# Booster.net
KiCad netlist of a schematic drawn in Altium Designer
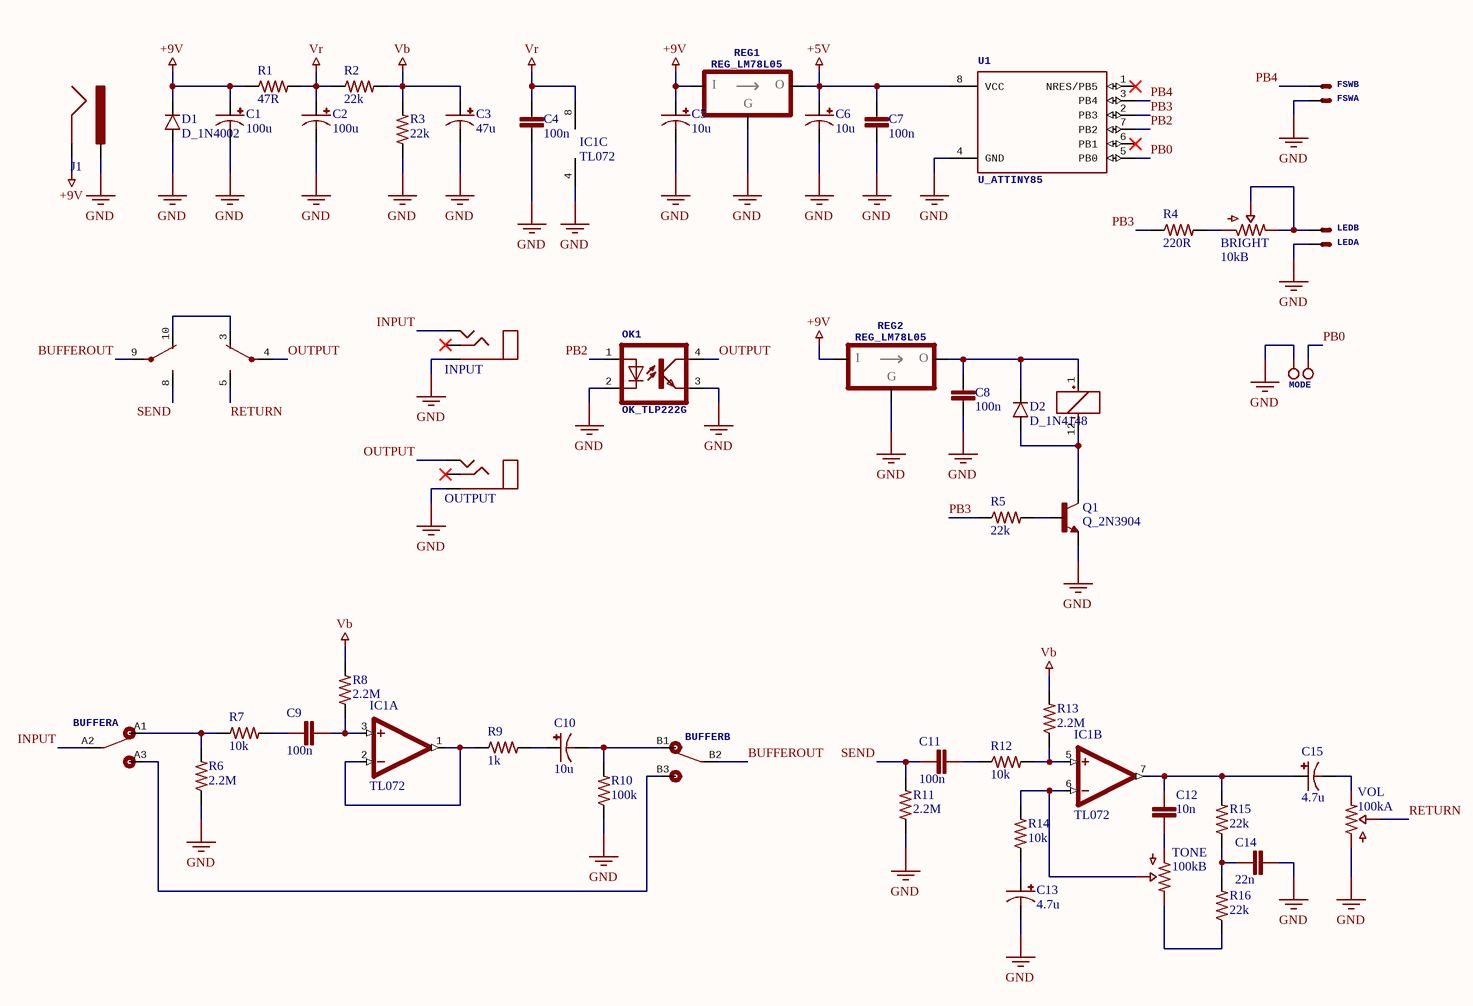
[diagram p0: Booster.SchDoc]

(export (version "E")
  (design (tool "Eeschema 10.0.6"))
  (components
    (comp (ref "BRIGHT")
      (value "10kB")
      (footprint "BOURNS_3362P")
      (description "10k Lin 3362P trimmer")
      (libsource (lib "Pedals") (part "TRIM_10kB_3362P"))
    )
    (comp (ref "BUFFER")
      (value "DPDT")
      (footprint "DPDT_SLIDE")
      (description "DPDT slide switch ON/ON")
      (libsource (lib "Pedals") (part "SW_SLIDE_DPDT_ON-ON"))
    )
    (comp (ref "C1")
      (value "100u")
      (footprint "ELEC_063_025")
      (description "100u 25V electrolytic capacitor")
      (libsource (lib "Pedals") (part "C_ELEC_100u_25V"))
    )
    (comp (ref "C2")
      (value "100u")
      (footprint "ELEC_063_025")
      (description "100u 25V electrolytic capacitor")
      (libsource (lib "Pedals") (part "C_ELEC_100u_25V"))
    )
    (comp (ref "C3")
      (value "47u")
      (footprint "ELEC_050_020")
      (description "47u 25V electrolytic capacitor")
      (libsource (lib "Pedals") (part "C_ELEC_47u_25V"))
    )
    (comp (ref "C4")
      (value "100n")
      (footprint "CER_050")
      (description "100n MLCC X7R radial capacitor")
      (libsource (lib "Pedals") (part "C_CER_100n"))
    )
    (comp (ref "C5")
      (value "10u")
      (footprint "ELEC_050_020")
      (description "10u 50V electrolytic capacitor")
      (libsource (lib "Pedals") (part "C_ELEC_10u_50V"))
    )
    (comp (ref "C6")
      (value "10u")
      (footprint "ELEC_050_020")
      (description "10u 50V electrolytic capacitor")
      (libsource (lib "Pedals") (part "C_ELEC_10u_50V"))
    )
    (comp (ref "C7")
      (value "100n")
      (footprint "CER_050")
      (description "100n MLCC X7R radial capacitor")
      (libsource (lib "") (part "C_CER_100n_1"))
    )
    (comp (ref "C8")
      (value "100n")
      (footprint "CER_050")
      (description "100n MLCC X7R radial capacitor")
      (libsource (lib "Pedals") (part "C_CER_100n"))
    )
    (comp (ref "C9")
      (value "100n")
      (footprint "FILMBOX_SMALL")
      (description "100n 100V polyester film box capacitor")
      (libsource (lib "Pedals") (part "C_FILMBOX_100n"))
    )
    (comp (ref "C10")
      (value "10u")
      (footprint "ELEC_LESR_050_020")
      (description "10u 50V Low ESR ectrolytic capacitor")
      (libsource (lib "Pedals") (part "C_ELEC_LESR_10u_50V"))
    )
    (comp (ref "C11")
      (value "100n")
      (footprint "FILMBOX_SMALL")
      (description "100n 100V polyester film box capacitor")
      (libsource (lib "Pedals") (part "C_FILMBOX_100n"))
    )
    (comp (ref "C12")
      (value "10n")
      (footprint "FILMBOX_SMALL")
      (description "10n 100V polyester film box capacitor")
      (libsource (lib "Pedals") (part "C_FILMBOX_10n"))
    )
    (comp (ref "C13")
      (value "4.7u")
      (footprint "ELEC_LESR_050_020")
      (description "4.7u 50V Low ESR ectrolytic capacitor")
      (libsource (lib "") (part "C_ELEC_LESR_4.7u_50V_1"))
    )
    (comp (ref "C14")
      (value "22n")
      (footprint "FILMBOX_SMALL")
      (description "22n 100V polyester film box capacitor")
      (libsource (lib "Pedals") (part "C_FILMBOX_22n"))
    )
    (comp (ref "C15")
      (value "4.7u")
      (footprint "ELEC_LESR_050_020")
      (description "4.7u 50V Low ESR ectrolytic capacitor")
      (libsource (lib "Pedals") (part "C_ELEC_LESR_4.7u_50V"))
    )
    (comp (ref "D1")
      (value "D_1N4002")
      (footprint "DO41_2")
      (description "1N4002")
      (libsource (lib "Pedals") (part "D_1N4002"))
    )
    (comp (ref "D2")
      (value "D_1N4148")
      (footprint "DO35_2")
      (description "1N4148")
      (libsource (lib "Pedals") (part "D_1N4148"))
    )
    (comp (ref "FSW")
      (value "J_JST-XH-02")
      (footprint "JST-XH-02")
      (description "2 Pins male XH header")
      (libsource (lib "Pedals") (part "J_JST-XH-02"))
    )
    (comp (ref "IC1") (value "TL072") (footprint "DIL8") (libsource (lib "Pedals") (part "IC_TL072")))
    (comp (ref "INPUT")
      (value "J_STEREO")
      (footprint "STEREO")
      (description "6.35mm stereo insulated socket jack PCB mounted")
      (libsource (lib "Pedals") (part "J_STEREO"))
    )
    (comp (ref "J1")
      (value "J_DC_JACK")
      (footprint "DC_JACK")
      (description "DC Power jack 2.1mm barrel")
      (libsource (lib "Pedals") (part "J_DC_JACK"))
    )
    (comp (ref "K1")
      (value "K_NA5W-K")
      (footprint "NA5")
      (description "NA5W-K")
      (libsource (lib "Pedals") (part "K_NA5W-K"))
    )
    (comp (ref "LED")
      (value "J_JST-XH-02")
      (footprint "JST-XH-02")
      (description "2 Pins male XH header")
      (libsource (lib "Pedals") (part "J_JST-XH-02"))
    )
    (comp (ref "MODE")
      (value "J_HEADER_2PINS")
      (footprint "HEADER_2PINS")
      (description "2 Pins male header")
      (libsource (lib "Pedals") (part "J_HEADER_2PINS"))
    )
    (comp (ref "OK1")
      (value "OK_TLP222G")
      (footprint "DIL4")
      (description "TLP222G")
      (libsource (lib "Pedals") (part "OK_TLP222G"))
    )
    (comp (ref "OUTPUT")
      (value "J_STEREO")
      (footprint "STEREO")
      (description "6.35mm stereo insulated socket jack PCB mounted")
      (libsource (lib "Pedals") (part "J_STEREO"))
    )
    (comp (ref "Q1")
      (value "Q_2N3904")
      (footprint "TO92")
      (description "2N3904")
      (libsource (lib "Pedals") (part "Q_2N3904"))
    )
    (comp (ref "R1")
      (value "47R")
      (footprint "R_3_47R_025W")
      (description "47R metal film 1/4W Resistor")
      (libsource (lib "Pedals") (part "R_3_47R_025W"))
    )
    (comp (ref "R2")
      (value "22k")
      (footprint "R_3_22k_025W")
      (description "22k metal film 1/4W Resistor")
      (libsource (lib "Pedals") (part "R_3_22k_025W"))
    )
    (comp (ref "R3")
      (value "22k")
      (footprint "R_3_22k_025W")
      (description "22k metal film 1/4W Resistor")
      (libsource (lib "Pedals") (part "R_3_22k_025W"))
    )
    (comp (ref "R4")
      (value "220R")
      (footprint "R_3_220R_025W")
      (description "220R metal film 1/4W Resistor")
      (libsource (lib "Pedals") (part "R_3_220R_025W"))
    )
    (comp (ref "R5")
      (value "22k")
      (footprint "R_3_22k_025W")
      (description "22k metal film 1/4W Resistor")
      (libsource (lib "Pedals") (part "R_3_22k_025W"))
    )
    (comp (ref "R6")
      (value "2.2M")
      (footprint "R_3_2,2M_025W")
      (description "2.2M metal film 1/4W Resistor")
      (libsource (lib "Pedals") (part "R_3_2.2M_025W"))
    )
    (comp (ref "R7")
      (value "10k")
      (footprint "R_3_10k_025W")
      (description "10k metal film 1/4W Resistor")
      (libsource (lib "Pedals") (part "R_3_10k_025W"))
    )
    (comp (ref "R8")
      (value "2.2M")
      (footprint "R_3_2,2M_025W")
      (description "2.2M metal film 1/4W Resistor")
      (libsource (lib "Pedals") (part "R_3_2.2M_025W"))
    )
    (comp (ref "R9")
      (value "1k")
      (footprint "R_3_1k_025W")
      (description "1k metal film 1/4W Resistor")
      (libsource (lib "Pedals") (part "R_3_1k_025W"))
    )
    (comp (ref "R10")
      (value "100k")
      (footprint "R_3_100k_025W")
      (description "100k metal film 1/4W Resistor")
      (libsource (lib "Pedals") (part "R_3_100k_025W"))
    )
    (comp (ref "R11")
      (value "2.2M")
      (footprint "R_3_2,2M_025W")
      (description "2.2M metal film 1/4W Resistor")
      (libsource (lib "Pedals") (part "R_3_2.2M_025W"))
    )
    (comp (ref "R12")
      (value "10k")
      (footprint "R_3_10k_025W")
      (description "10k metal film 1/4W Resistor")
      (libsource (lib "Pedals") (part "R_3_10k_025W"))
    )
    (comp (ref "R13")
      (value "2.2M")
      (footprint "R_3_2,2M_025W")
      (description "2.2M metal film 1/4W Resistor")
      (libsource (lib "Pedals") (part "R_3_2.2M_025W"))
    )
    (comp (ref "R14")
      (value "10k")
      (footprint "R_3_10k_025W")
      (description "10k metal film 1/4W Resistor")
      (libsource (lib "Pedals") (part "R_3_10k_025W"))
    )
    (comp (ref "R15")
      (value "22k")
      (footprint "R_3_22k_025W")
      (description "22k metal film 1/4W Resistor")
      (libsource (lib "Pedals") (part "R_3_22k_025W"))
    )
    (comp (ref "R16")
      (value "22k")
      (footprint "R_3_22k_025W")
      (description "22k metal film 1/4W Resistor")
      (libsource (lib "Pedals") (part "R_3_22k_025W"))
    )
    (comp (ref "REG1")
      (value "REG_LM78L05")
      (footprint "TO92")
      (description "78L05")
      (libsource (lib "Pedals") (part "REG_LM78L05"))
    )
    (comp (ref "REG2")
      (value "REG_LM78L05")
      (footprint "TO92")
      (description "78L05")
      (libsource (lib "Pedals") (part "REG_LM78L05"))
    )
    (comp (ref "TONE")
      (value "100kB")
      (footprint "ALPHA_16mm_BOTTOM")
      (description "100k Lin potentiometer round shaft")
      (libsource (lib "Pedals") (part "POT_100kB_ALPHA_16mm"))
    )
    (comp (ref "U1")
      (value "U_ATTINY85")
      (footprint "DIP8")
      (description "ATTINY85-20PU")
      (libsource (lib "Pedals") (part "U_ATTINY85"))
    )
    (comp (ref "VOL")
      (value "100kA")
      (footprint "ALPHA_16mm_BOTTOM")
      (description "100k Log potentiometer round shaft")
      (libsource (lib "Pedals") (part "POT_100kA_ALPHA_16mm"))
    )
  )
  (nets
    (net (code "1") (name "+5V") (class "Default")
      (node (ref "C6") (pin "+") (pinfunction "+_+") (pintype "passive"))
      (node (ref "C7") (pin "2") (pinfunction "2_2") (pintype "passive"))
      (node (ref "REG1") (pin "3") (pinfunction "VO_3") (pintype "power_in"))
      (node (ref "U1") (pin "8") (pinfunction "VCC_8") (pintype "power_in"))
    )
    (net (code "2") (name "+9V") (class "Default")
      (node (ref "C1") (pin "+") (pinfunction "+_+") (pintype "passive"))
      (node (ref "C5") (pin "+") (pinfunction "+_+") (pintype "passive"))
      (node (ref "D1") (pin "C") (pinfunction "C_C") (pintype "passive"))
      (node (ref "J1") (pin "GND") (pinfunction "GND_GND") (pintype "passive"))
      (node (ref "R1") (pin "1") (pinfunction "1_1") (pintype "passive"))
      (node (ref "REG1") (pin "1") (pinfunction "VI_1") (pintype "power_in"))
      (node (ref "REG2") (pin "1") (pinfunction "VI_1") (pintype "power_in"))
    )
    (net (code "3") (name "/BUFFEROUT") (class "Default")
      (node (ref "BUFFER") (pin "B2") (pinfunction "2_B2") (pintype "passive"))
      (node (ref "K1") (pin "9") (pinfunction "P_9") (pintype "passive"))
    )
    (net (code "4") (name "/INPUT") (class "Default")
      (node (ref "BUFFER") (pin "A2") (pinfunction "2_A2") (pintype "passive"))
      (node (ref "INPUT") (pin "T") (pinfunction "T_T") (pintype "passive"))
    )
    (net (code "5") (name "/OUTPUT") (class "Default")
      (node (ref "K1") (pin "4") (pinfunction "P_4") (pintype "passive"))
      (node (ref "OK1") (pin "4") (pinfunction "COL_4") (pintype "passive"))
      (node (ref "OUTPUT") (pin "T") (pinfunction "T_T") (pintype "passive"))
    )
    (net (code "6") (name "/PB0") (class "Default")
      (node (ref "MODE") (pin "2") (pinfunction "2_2") (pintype "passive"))
      (node (ref "U1") (pin "5") (pinfunction "PB0_5") (pintype "bidirectional"))
    )
    (net (code "7") (name "/PB2") (class "Default")
      (node (ref "OK1") (pin "1") (pinfunction "A_1") (pintype "passive"))
      (node (ref "U1") (pin "7") (pinfunction "PB2_7") (pintype "bidirectional"))
    )
    (net (code "8") (name "/PB3") (class "Default")
      (node (ref "R4") (pin "1") (pinfunction "1_1") (pintype "passive"))
      (node (ref "R5") (pin "1") (pinfunction "1_1") (pintype "passive"))
      (node (ref "U1") (pin "2") (pinfunction "PB3_2") (pintype "bidirectional"))
    )
    (net (code "9") (name "/PB4") (class "Default")
      (node (ref "FSW") (pin "1") (pinfunction "S_1") (pintype "passive"))
      (node (ref "U1") (pin "3") (pinfunction "PB4_3") (pintype "bidirectional"))
    )
    (net (code "10") (name "/RETURN") (class "Default")
      (node (ref "K1") (pin "5") (pinfunction "S_5") (pintype "passive"))
      (node (ref "VOL") (pin "2") (pinfunction "2_2") (pintype "passive"))
    )
    (net (code "11") (name "/SEND") (class "Default")
      (node (ref "C11") (pin "2") (pinfunction "2_2") (pintype "passive"))
      (node (ref "K1") (pin "8") (pinfunction "S_8") (pintype "passive"))
      (node (ref "R11") (pin "2") (pinfunction "2_2") (pintype "passive"))
    )
    (net (code "12") (name "GND") (class "Default")
      (node (ref "C1") (pin "-") (pinfunction "-_-") (pintype "passive"))
      (node (ref "C13") (pin "-") (pinfunction "-_-") (pintype "passive"))
      (node (ref "C14") (pin "1") (pinfunction "1_1") (pintype "passive"))
      (node (ref "C2") (pin "-") (pinfunction "-_-") (pintype "passive"))
      (node (ref "C3") (pin "-") (pinfunction "-_-") (pintype "passive"))
      (node (ref "C4") (pin "2") (pinfunction "2_2") (pintype "passive"))
      (node (ref "C5") (pin "-") (pinfunction "-_-") (pintype "passive"))
      (node (ref "C6") (pin "-") (pinfunction "-_-") (pintype "passive"))
      (node (ref "C7") (pin "1") (pinfunction "1_1") (pintype "passive"))
      (node (ref "C8") (pin "2") (pinfunction "2_2") (pintype "passive"))
      (node (ref "D1") (pin "A") (pinfunction "A_A") (pintype "passive"))
      (node (ref "FSW") (pin "2") (pinfunction "S_2") (pintype "passive"))
      (node (ref "IC1") (pin "4") (pinfunction "V-_4") (pintype "power_in"))
      (node (ref "INPUT") (pin "S") (pinfunction "S_S") (pintype "passive"))
      (node (ref "J1") (pin "PWR") (pinfunction "PWR_PWR") (pintype "passive"))
      (node (ref "LED") (pin "2") (pinfunction "S_2") (pintype "passive"))
      (node (ref "MODE") (pin "1") (pinfunction "1_1") (pintype "passive"))
      (node (ref "OK1") (pin "2") (pinfunction "C_2") (pintype "passive"))
      (node (ref "OK1") (pin "3") (pinfunction "EMIT_3") (pintype "passive"))
      (node (ref "OUTPUT") (pin "S") (pinfunction "S_S") (pintype "passive"))
      (node (ref "Q1") (pin "3") (pinfunction "E_3") (pintype "passive"))
      (node (ref "R10") (pin "1") (pinfunction "1_1") (pintype "passive"))
      (node (ref "R11") (pin "1") (pinfunction "1_1") (pintype "passive"))
      (node (ref "R3") (pin "1") (pinfunction "1_1") (pintype "passive"))
      (node (ref "R6") (pin "1") (pinfunction "1_1") (pintype "passive"))
      (node (ref "REG1") (pin "2") (pinfunction "GND_2") (pintype "power_in"))
      (node (ref "REG2") (pin "2") (pinfunction "GND_2") (pintype "power_in"))
      (node (ref "U1") (pin "4") (pinfunction "GND_4") (pintype "power_in"))
      (node (ref "VOL") (pin "1") (pinfunction "1_1") (pintype "passive"))
    )
    (net (code "13") (name "Net-(BRIGHT-Pad1)") (class "Default")
      (node (ref "BRIGHT") (pin "1") (pinfunction "1_1") (pintype "passive"))
      (node (ref "R4") (pin "2") (pinfunction "2_2") (pintype "passive"))
    )
    (net (code "14") (name "Net-(BUFFERA-1)") (class "Default")
      (node (ref "BUFFER") (pin "A1") (pinfunction "1_A1") (pintype "passive"))
      (node (ref "R6") (pin "2") (pinfunction "2_2") (pintype "passive"))
      (node (ref "R7") (pin "1") (pinfunction "1_1") (pintype "passive"))
    )
    (net (code "15") (name "Net-(BUFFERA-3)") (class "Default")
      (node (ref "BUFFER") (pin "A3") (pinfunction "3_A3") (pintype "passive"))
      (node (ref "BUFFER") (pin "B3") (pinfunction "3_B3") (pintype "passive"))
    )
    (net (code "16") (name "Net-(BUFFERB-1)") (class "Default")
      (node (ref "BUFFER") (pin "B1") (pinfunction "1_B1") (pintype "passive"))
      (node (ref "C10") (pin "-") (pinfunction "-_-") (pintype "passive"))
      (node (ref "R10") (pin "2") (pinfunction "2_2") (pintype "passive"))
    )
    (net (code "17") (name "Net-(C9-Pad2)") (class "Default")
      (node (ref "C9") (pin "2") (pinfunction "2_2") (pintype "passive"))
      (node (ref "R7") (pin "2") (pinfunction "2_2") (pintype "passive"))
    )
    (net (code "18") (name "Net-(C10-Pad+)") (class "Default")
      (node (ref "C10") (pin "+") (pinfunction "+_+") (pintype "passive"))
      (node (ref "R9") (pin "2") (pinfunction "2_2") (pintype "passive"))
    )
    (net (code "19") (name "Net-(C11-Pad1)") (class "Default")
      (node (ref "C11") (pin "1") (pinfunction "1_1") (pintype "passive"))
      (node (ref "R12") (pin "1") (pinfunction "1_1") (pintype "passive"))
    )
    (net (code "20") (name "Net-(C12-Pad2)") (class "Default")
      (node (ref "C12") (pin "2") (pinfunction "2_2") (pintype "passive"))
      (node (ref "TONE") (pin "1") (pinfunction "1_1") (pintype "passive"))
    )
    (net (code "21") (name "Net-(C13-Pad+)") (class "Default")
      (node (ref "C13") (pin "+") (pinfunction "+_+") (pintype "passive"))
      (node (ref "R14") (pin "1") (pinfunction "1_1") (pintype "passive"))
    )
    (net (code "22") (name "Net-(C14-Pad2)") (class "Default")
      (node (ref "C14") (pin "2") (pinfunction "2_2") (pintype "passive"))
      (node (ref "R15") (pin "1") (pinfunction "1_1") (pintype "passive"))
      (node (ref "R16") (pin "2") (pinfunction "2_2") (pintype "passive"))
    )
    (net (code "23") (name "Net-(C15-Pad-)") (class "Default")
      (node (ref "C15") (pin "-") (pinfunction "-_-") (pintype "passive"))
      (node (ref "VOL") (pin "3") (pinfunction "3_3") (pintype "passive"))
    )
    (net (code "24") (name "Net-(IC1A-+IN)") (class "Default")
      (node (ref "C9") (pin "1") (pinfunction "1_1") (pintype "passive"))
      (node (ref "IC1") (pin "3") (pinfunction "+IN_3") (pintype "input"))
      (node (ref "R8") (pin "1") (pinfunction "1_1") (pintype "passive"))
    )
    (net (code "25") (name "Net-(IC1A--IN)") (class "Default")
      (node (ref "IC1") (pin "1") (pinfunction "OUT_1") (pintype "output"))
      (node (ref "IC1") (pin "2") (pinfunction "-IN_2") (pintype "input"))
      (node (ref "R9") (pin "1") (pinfunction "1_1") (pintype "passive"))
    )
    (net (code "26") (name "Net-(IC1B-+IN)") (class "Default")
      (node (ref "IC1") (pin "5") (pinfunction "+IN_5") (pintype "input"))
      (node (ref "R12") (pin "2") (pinfunction "2_2") (pintype "passive"))
      (node (ref "R13") (pin "1") (pinfunction "1_1") (pintype "passive"))
    )
    (net (code "27") (name "Net-(IC1B--IN)") (class "Default")
      (node (ref "IC1") (pin "6") (pinfunction "-IN_6") (pintype "input"))
      (node (ref "R14") (pin "2") (pinfunction "2_2") (pintype "passive"))
      (node (ref "TONE") (pin "2") (pinfunction "2_2") (pintype "passive"))
    )
    (net (code "28") (name "Net-(IC1B-OUT)") (class "Default")
      (node (ref "C12") (pin "1") (pinfunction "1_1") (pintype "passive"))
      (node (ref "C15") (pin "+") (pinfunction "+_+") (pintype "passive"))
      (node (ref "IC1") (pin "7") (pinfunction "OUT_7") (pintype "output"))
      (node (ref "R15") (pin "2") (pinfunction "2_2") (pintype "passive"))
    )
    (net (code "29") (name "Net-(K1A-+)") (class "Default")
      (node (ref "C8") (pin "1") (pinfunction "1_1") (pintype "passive"))
      (node (ref "D2") (pin "C") (pinfunction "C_C") (pintype "passive"))
      (node (ref "K1") (pin "1") (pinfunction "+_1") (pintype "passive"))
      (node (ref "REG2") (pin "3") (pinfunction "VO_3") (pintype "power_in"))
    )
    (net (code "30") (name "Net-(K1A--)") (class "Default")
      (node (ref "D2") (pin "A") (pinfunction "A_A") (pintype "passive"))
      (node (ref "K1") (pin "12") (pinfunction "-_12") (pintype "passive"))
      (node (ref "Q1") (pin "1") (pinfunction "C_1") (pintype "passive"))
    )
    (net (code "31") (name "Net-(K1B-O)") (class "Default")
      (node (ref "K1") (pin "10") (pinfunction "O_10") (pintype "passive"))
      (node (ref "K1") (pin "3") (pinfunction "O_3") (pintype "passive"))
    )
    (net (code "32") (name "Net-(LEDB-S)") (class "Default")
      (node (ref "BRIGHT") (pin "2") (pinfunction "2_2") (pintype "passive"))
      (node (ref "BRIGHT") (pin "3") (pinfunction "3_3") (pintype "passive"))
      (node (ref "LED") (pin "1") (pinfunction "S_1") (pintype "passive"))
    )
    (net (code "33") (name "Net-(Q1-B)") (class "Default")
      (node (ref "Q1") (pin "2") (pinfunction "B_2") (pintype "passive"))
      (node (ref "R5") (pin "2") (pinfunction "2_2") (pintype "passive"))
    )
    (net (code "34") (name "Net-(R16-Pad1)") (class "Default")
      (node (ref "R16") (pin "1") (pinfunction "1_1") (pintype "passive"))
      (node (ref "TONE") (pin "3") (pinfunction "3_3") (pintype "passive"))
    )
    (net (code "35") (name "Vb") (class "Default")
      (node (ref "C3") (pin "+") (pinfunction "+_+") (pintype "passive"))
      (node (ref "R13") (pin "2") (pinfunction "2_2") (pintype "passive"))
      (node (ref "R2") (pin "2") (pinfunction "2_2") (pintype "passive"))
      (node (ref "R3") (pin "2") (pinfunction "2_2") (pintype "passive"))
      (node (ref "R8") (pin "2") (pinfunction "2_2") (pintype "passive"))
    )
    (net (code "36") (name "Vr") (class "Default")
      (node (ref "C2") (pin "+") (pinfunction "+_+") (pintype "passive"))
      (node (ref "C4") (pin "1") (pinfunction "1_1") (pintype "passive"))
      (node (ref "IC1") (pin "8") (pinfunction "V+_8") (pintype "power_in"))
      (node (ref "R1") (pin "2") (pinfunction "2_2") (pintype "passive"))
      (node (ref "R2") (pin "1") (pinfunction "1_1") (pintype "passive"))
    )
    (net (code "37") (name "unconnected-(INPUT-PadR)") (class "Default")
      (node (ref "INPUT") (pin "R") (pinfunction "R_R") (pintype "passive+no_connect"))
    )
    (net (code "38") (name "unconnected-(OUTPUT-PadR)") (class "Default")
      (node (ref "OUTPUT") (pin "R") (pinfunction "R_R") (pintype "passive+no_connect"))
    )
    (net (code "39") (name "unconnected-(U1-NRES{slash}PB5-Pad1)") (class "Default")
      (node (ref "U1") (pin "1") (pinfunction "NRES/PB5_1") (pintype "bidirectional+no_connect"))
    )
    (net (code "40") (name "unconnected-(U1-PB1-Pad6)") (class "Default")
      (node (ref "U1") (pin "6") (pinfunction "PB1_6") (pintype "bidirectional+no_connect"))
    )
  )
)
